# openSX70-usb-charger.net
KiCad netlist of a schematic drawn in EAGLE
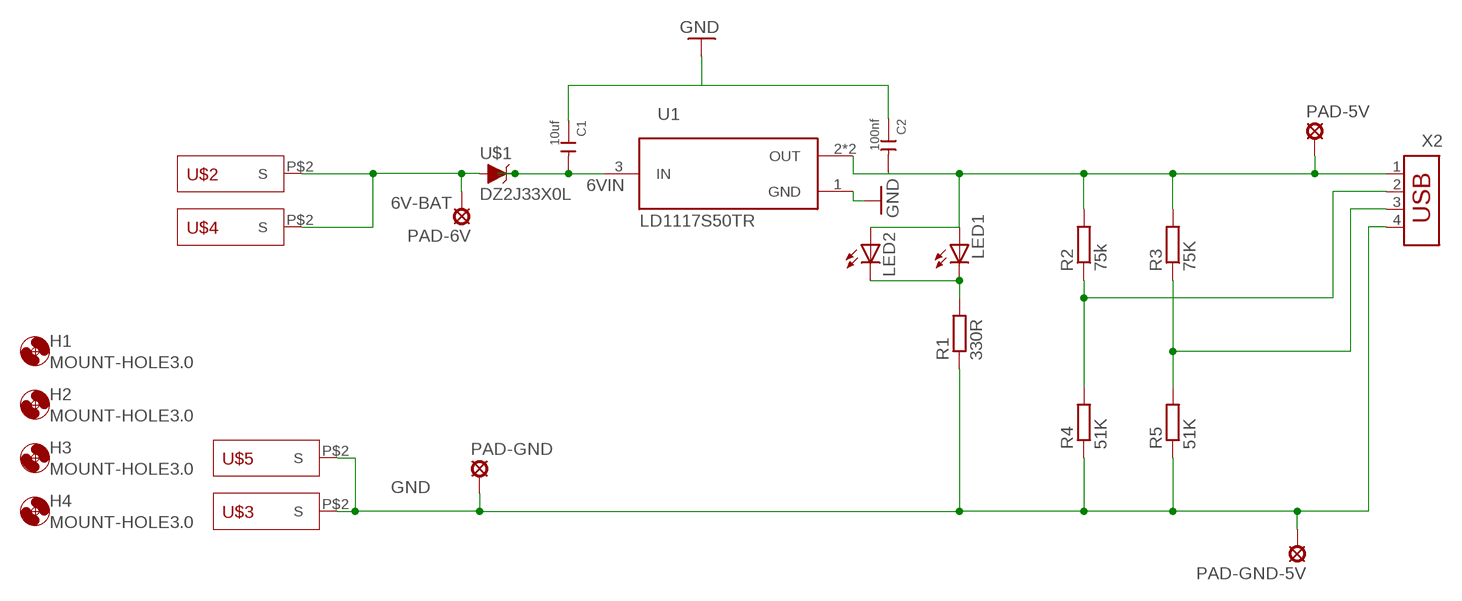
[diagram p0: schematic, sheet 1]

(export (version "E")
  (design (tool "Eeschema 10.0.6"))
  (components
    (comp (ref "C1")
      (value "10uf")
      (footprint "eagle-import:C0603")
      (fields (field (name "MPN") "CC0603KRX5R6BB106"))
      (libsource (lib "eagle-import") (part "CERAMIC-10UF-10V-10%-X5R(0603)"))
    )
    (comp (ref "C2")
      (value "100nf")
      (footprint "eagle-import:C0603")
      (fields (field (name "MPN") "CC0603KRX7R9BB104"))
      (libsource (lib "eagle-import") (part "CERAMIC-100NF-50V-10%-X7R(0603)"))
    )
    (comp (ref "H1")
      (value "MOUNT-HOLE3.0")
      (footprint "eagle-import:3,0")
      (libsource (lib "eagle-import") (part "MOUNT-HOLE3.0"))
    )
    (comp (ref "H2")
      (value "MOUNT-HOLE3.0")
      (footprint "eagle-import:3,0")
      (libsource (lib "eagle-import") (part "MOUNT-HOLE3.0"))
    )
    (comp (ref "H3")
      (value "MOUNT-HOLE3.0")
      (footprint "eagle-import:3,0")
      (libsource (lib "eagle-import") (part "MOUNT-HOLE3.0"))
    )
    (comp (ref "H4")
      (value "MOUNT-HOLE3.0")
      (footprint "eagle-import:3,0")
      (libsource (lib "eagle-import") (part "MOUNT-HOLE3.0"))
    )
    (comp (ref "LED1")
      (value "LED5MM")
      (footprint "eagle-import:LED5MM")
      (libsource (lib "eagle-import") (part "LED5MM"))
    )
    (comp (ref "LED2")
      (value "LEDCHIPLED_0805")
      (footprint "eagle-import:CHIPLED_0805")
      (libsource (lib "eagle-import") (part "LEDCHIPLED_0805"))
    )
    (comp (ref "PAD-5V")
      (value "LSP13")
      (footprint "eagle-import:LSP13")
      (libsource (lib "eagle-import") (part "LSP13"))
    )
    (comp (ref "PAD-6V")
      (value "LSP13")
      (footprint "eagle-import:LSP13")
      (libsource (lib "eagle-import") (part "LSP13"))
    )
    (comp (ref "PAD-GND")
      (value "LSP13")
      (footprint "eagle-import:LSP13")
      (libsource (lib "eagle-import") (part "LSP13"))
    )
    (comp (ref "PAD-GND-5V")
      (value "LSP13")
      (footprint "eagle-import:LSP13")
      (libsource (lib "eagle-import") (part "LSP13"))
    )
    (comp (ref "R1")
      (value "330R")
      (footprint "eagle-import:R0603")
      (libsource (lib "eagle-import") (part "R-EU_R0603"))
    )
    (comp (ref "R2")
      (value "75k")
      (footprint "eagle-import:R0603")
      (libsource (lib "eagle-import") (part "R-EU_R0603"))
    )
    (comp (ref "R3")
      (value "75K")
      (footprint "eagle-import:R0603")
      (libsource (lib "eagle-import") (part "R-EU_R0603"))
    )
    (comp (ref "R4")
      (value "51K")
      (footprint "eagle-import:R0603")
      (libsource (lib "eagle-import") (part "R-EU_R0603"))
    )
    (comp (ref "R5")
      (value "51K")
      (footprint "eagle-import:R0603")
      (libsource (lib "eagle-import") (part "R-EU_R0603"))
    )
    (comp (ref "U$1")
      (value "DZ2J33X0L")
      (footprint "eagle-import:SMINI2")
      (libsource (lib "eagle-import") (part "DZ2J33X0L"))
    )
    (comp (ref "U$2")
      (value "BATTERY-PAD")
      (footprint "eagle-import:BATTERY-PAD")
      (libsource (lib "eagle-import") (part "BATTERY-PAD"))
    )
    (comp (ref "U$3")
      (value "BATTERY-PAD")
      (footprint "eagle-import:BATTERY-PAD")
      (libsource (lib "eagle-import") (part "BATTERY-PAD"))
    )
    (comp (ref "U$4")
      (value "BATTERY-PAD")
      (footprint "eagle-import:BATTERY-PAD")
      (libsource (lib "eagle-import") (part "BATTERY-PAD"))
    )
    (comp (ref "U$5")
      (value "BATTERY-PAD")
      (footprint "eagle-import:BATTERY-PAD")
      (libsource (lib "eagle-import") (part "BATTERY-PAD"))
    )
    (comp (ref "U1")
      (value "LD1117S50TR")
      (footprint "eagle-import:LD1117S50TR_SOT230P700X180-4N")
      (fields (field (name "MANUFACTURER") "ST Microelectronics"))
      (libsource (lib "eagle-import") (part "LD1117S50TR"))
    )
    (comp (ref "X2")
      (value "USB-787616")
      (footprint "eagle-import:USB")
      (libsource (lib "eagle-import") (part "USB-787616"))
    )
  )
  (nets
    (net (code "1") (name "/6V-BAT") (class "Default")
      (node (ref "PAD-6V") (pin "MP") (pinfunction "MP_MP") (pintype "passive"))
      (node (ref "U$1") (pin "P$2") (pinfunction "A_P$2") (pintype "passive"))
      (node (ref "U$2") (pin "P$2") (pinfunction "S_P$2") (pintype "bidirectional"))
      (node (ref "U$4") (pin "P$2") (pinfunction "S_P$2") (pintype "bidirectional"))
    )
    (net (code "2") (name "/6VIN") (class "Default")
      (node (ref "C1") (pin "2") (pinfunction "2_2") (pintype "passive"))
      (node (ref "U$1") (pin "P$1") (pinfunction "C_P$1") (pintype "passive"))
      (node (ref "U1") (pin "3") (pinfunction "IN_3") (pintype "input"))
    )
    (net (code "3") (name "GND") (class "Default")
      (node (ref "C1") (pin "1") (pinfunction "1_1") (pintype "passive"))
      (node (ref "C2") (pin "1") (pinfunction "1_1") (pintype "passive"))
      (node (ref "PAD-GND") (pin "MP") (pinfunction "MP_MP") (pintype "passive"))
      (node (ref "PAD-GND-5V") (pin "MP") (pinfunction "MP_MP") (pintype "passive"))
      (node (ref "R1") (pin "1") (pinfunction "1_1") (pintype "passive"))
      (node (ref "R4") (pin "1") (pinfunction "1_1") (pintype "passive"))
      (node (ref "R5") (pin "1") (pinfunction "1_1") (pintype "passive"))
      (node (ref "U$3") (pin "P$2") (pinfunction "S_P$2") (pintype "bidirectional"))
      (node (ref "U$5") (pin "P$2") (pinfunction "S_P$2") (pintype "bidirectional"))
      (node (ref "U1") (pin "1") (pinfunction "GND_1") (pintype "power_in"))
      (node (ref "X2") (pin "4") (pinfunction "4_4") (pintype "passive"))
    )
    (net (code "4") (name "Net-(C2-Pad2)") (class "Default")
      (node (ref "C2") (pin "2") (pinfunction "2_2") (pintype "passive"))
      (node (ref "LED1") (pin "A") (pinfunction "A_A") (pintype "passive"))
      (node (ref "LED2") (pin "A") (pinfunction "A_A") (pintype "passive"))
      (node (ref "PAD-5V") (pin "MP") (pinfunction "MP_MP") (pintype "passive"))
      (node (ref "R2") (pin "2") (pinfunction "2_2") (pintype "passive"))
      (node (ref "R3") (pin "2") (pinfunction "2_2") (pintype "passive"))
      (node (ref "U1") (pin "2") (pinfunction "OUT_2") (pintype "output"))
      (node (ref "U1") (pin "4") (pinfunction "OUT_4") (pintype "output"))
      (node (ref "X2") (pin "1") (pinfunction "1_1") (pintype "passive"))
    )
    (net (code "5") (name "Net-(LED1-C)") (class "Default")
      (node (ref "LED1") (pin "K") (pinfunction "C_K") (pintype "passive"))
      (node (ref "LED2") (pin "C") (pinfunction "C_C") (pintype "passive"))
      (node (ref "R1") (pin "2") (pinfunction "2_2") (pintype "passive"))
    )
    (net (code "6") (name "Net-(R2-Pad1)") (class "Default")
      (node (ref "R2") (pin "1") (pinfunction "1_1") (pintype "passive"))
      (node (ref "R4") (pin "2") (pinfunction "2_2") (pintype "passive"))
      (node (ref "X2") (pin "2") (pinfunction "2_2") (pintype "passive"))
    )
    (net (code "7") (name "Net-(R3-Pad1)") (class "Default")
      (node (ref "R3") (pin "1") (pinfunction "1_1") (pintype "passive"))
      (node (ref "R5") (pin "2") (pinfunction "2_2") (pintype "passive"))
      (node (ref "X2") (pin "3") (pinfunction "3_3") (pintype "passive"))
    )
  )
)
